# RF_Module.net
KiCad netlist of a schematic drawn in Altium Designer
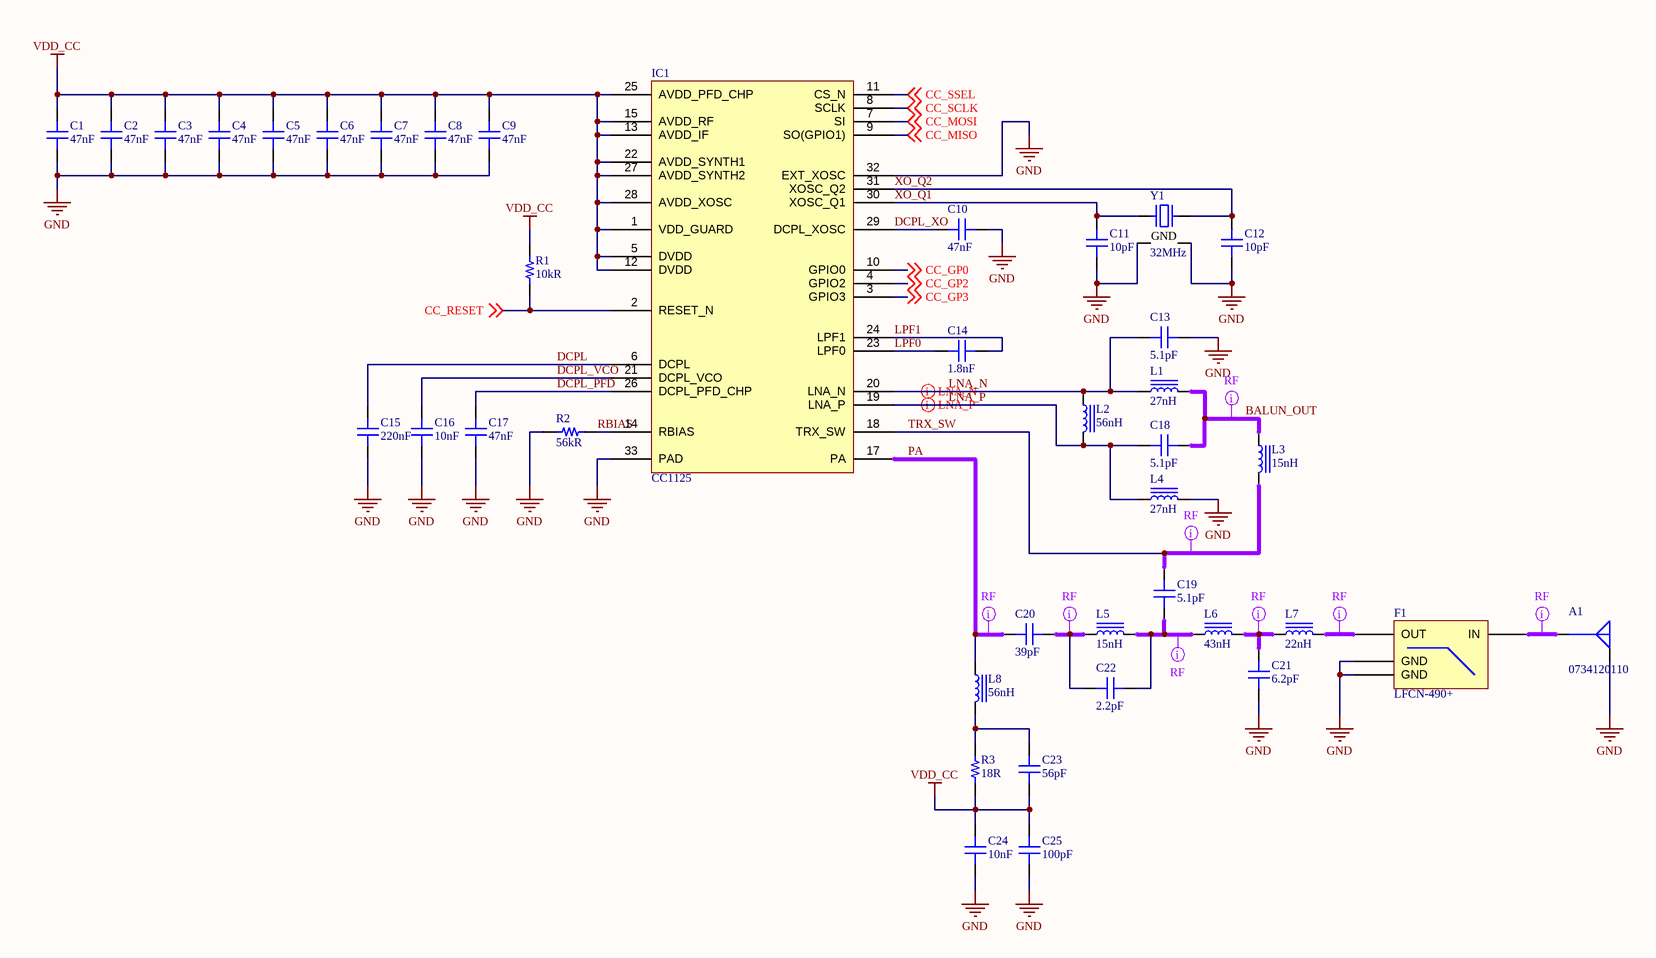
[diagram p0: RF Module.SchDoc]

(export (version "E")
  (design (tool "Eeschema 10.0.6"))
  (components
    (comp (ref "A1")
      (value "0734120110")
      (footprint "MOLEX SD-734120110")
      (description "Conn Micro Coaxial RCP 0Hz to 6GHz 50Ohm Solder ST SMD Gold Embossed T/R")
      (libsource (lib "SCH - RF - ANTENNA - BASIC ANTENNA") (part "Basic Antenna"))
    )
    (comp (ref "C1")
      (value "47nF")
      (footprint "CAP 0402/1005")
      (description "CAP CER 0.047UF 10V X7R 0402")
      (fields (field (name "TOLERANCE") "10%") (field (name "VOLTAGE") "16V"))
      (libsource (lib "SCH - PASSIVES - CAPACITOR") (part "Capacitor"))
    )
    (comp (ref "C2")
      (value "47nF")
      (footprint "CAP 0402/1005")
      (description "CAP CER 0.047UF 10V X7R 0402")
      (fields (field (name "TOLERANCE") "10%") (field (name "VOLTAGE") "16V"))
      (libsource (lib "SCH - PASSIVES - CAPACITOR") (part "Capacitor"))
    )
    (comp (ref "C3")
      (value "47nF")
      (footprint "CAP 0402/1005")
      (description "CAP CER 0.047UF 10V X7R 0402")
      (fields (field (name "TOLERANCE") "10%") (field (name "VOLTAGE") "16V"))
      (libsource (lib "SCH - PASSIVES - CAPACITOR") (part "Capacitor"))
    )
    (comp (ref "C4")
      (value "47nF")
      (footprint "CAP 0402/1005")
      (description "CAP CER 0.047UF 10V X7R 0402")
      (fields (field (name "TOLERANCE") "10%") (field (name "VOLTAGE") "16V"))
      (libsource (lib "SCH - PASSIVES - CAPACITOR") (part "Capacitor"))
    )
    (comp (ref "C5")
      (value "47nF")
      (footprint "CAP 0402/1005")
      (description "CAP CER 0.047UF 10V X7R 0402")
      (fields (field (name "TOLERANCE") "10%") (field (name "VOLTAGE") "16V"))
      (libsource (lib "SCH - PASSIVES - CAPACITOR") (part "Capacitor"))
    )
    (comp (ref "C6")
      (value "47nF")
      (footprint "CAP 0402/1005")
      (description "CAP CER 0.047UF 10V X7R 0402")
      (fields (field (name "TOLERANCE") "10%") (field (name "VOLTAGE") "16V"))
      (libsource (lib "SCH - PASSIVES - CAPACITOR") (part "Capacitor"))
    )
    (comp (ref "C7")
      (value "47nF")
      (footprint "CAP 0402/1005")
      (description "CAP CER 0.047UF 10V X7R 0402")
      (fields (field (name "TOLERANCE") "10%") (field (name "VOLTAGE") "16V"))
      (libsource (lib "SCH - PASSIVES - CAPACITOR") (part "Capacitor"))
    )
    (comp (ref "C8")
      (value "47nF")
      (footprint "CAP 0402/1005")
      (description "CAP CER 0.047UF 10V X7R 0402")
      (fields (field (name "TOLERANCE") "10%") (field (name "VOLTAGE") "16V"))
      (libsource (lib "SCH - PASSIVES - CAPACITOR") (part "Capacitor"))
    )
    (comp (ref "C9")
      (value "47nF")
      (footprint "CAP 0402/1005")
      (description "CAP CER 0.047UF 10V X7R 0402")
      (fields (field (name "TOLERANCE") "10%") (field (name "VOLTAGE") "16V"))
      (libsource (lib "SCH - PASSIVES - CAPACITOR") (part "Capacitor"))
    )
    (comp (ref "C10")
      (value "47nF")
      (footprint "CAP 0402/1005")
      (description "CAP CER 0.047UF 10V X7R 0402")
      (fields (field (name "TOLERANCE") "10%") (field (name "VOLTAGE") "16V"))
      (libsource (lib "SCH - PASSIVES - CAPACITOR") (part "Capacitor"))
    )
    (comp (ref "C11")
      (value "10pF")
      (footprint "CAP 0402/1005")
      (description "CAP CER 10PF 50V C0G/NPO 0402")
      (fields (field (name "TOLERANCE") "5%") (field (name "VOLTAGE") "50V"))
      (libsource (lib "SCH - PASSIVES - CAPACITOR") (part "Capacitor"))
    )
    (comp (ref "C12")
      (value "10pF")
      (footprint "CAP 0402/1005")
      (description "CAP CER 10PF 50V C0G/NPO 0402")
      (fields (field (name "TOLERANCE") "5%") (field (name "VOLTAGE") "50V"))
      (libsource (lib "SCH - PASSIVES - CAPACITOR") (part "Capacitor"))
    )
    (comp (ref "C13")
      (value "5.1pF")
      (footprint "CAP 0402/1005 RF")
      (description "CAP CER 5.1PF 50V C0G/NP0 0402")
      (fields (field (name "VOLTAGE") "50V"))
      (libsource (lib "SCH - PASSIVES - CAPACITOR") (part "Capacitor"))
    )
    (comp (ref "C14")
      (value "1.8nF")
      (footprint "CAP 0402/1005")
      (description "CAP CER 1800PF 50V X7R 0402")
      (fields (field (name "TOLERANCE") "10%"))
      (libsource (lib "SCH - PASSIVES - CAPACITOR") (part "Capacitor"))
    )
    (comp (ref "C15")
      (value "220nF")
      (footprint "CAP 0402/1005")
      (description "Cap Ceramic 0.22uF 10V X7R 10% SMD 0402 125C Paper T/R")
      (fields (field (name "TOLERANCE") "10%"))
      (libsource (lib "SCH - PASSIVES - CAPACITOR") (part "Capacitor"))
    )
    (comp (ref "C16")
      (value "10nF")
      (footprint "CAP 0402/1005")
      (description "TAIYO YUDEN - TMK105B7103KV-F - CERAMIC CAPACITOR 0.01UF, 25V, X7R, 10%, 0402, FULL REEL")
      (fields (field (name "TOLERANCE") "10%") (field (name "VOLTAGE") "25V"))
      (libsource (lib "SCH - PASSIVES - CAPACITOR") (part "Capacitor"))
    )
    (comp (ref "C17")
      (value "47nF")
      (footprint "CAP 0402/1005")
      (description "CAP CER 0.047UF 10V X7R 0402")
      (fields (field (name "TOLERANCE") "10%") (field (name "VOLTAGE") "16V"))
      (libsource (lib "SCH - PASSIVES - CAPACITOR") (part "Capacitor"))
    )
    (comp (ref "C18")
      (value "5.1pF")
      (footprint "CAP 0402/1005 RF")
      (description "CAP CER 5.1PF 50V C0G/NP0 0402")
      (fields (field (name "VOLTAGE") "50V"))
      (libsource (lib "SCH - PASSIVES - CAPACITOR") (part "Capacitor"))
    )
    (comp (ref "C19")
      (value "5.1pF")
      (footprint "CAP 0402/1005 RF")
      (description "CAP CER 5.1PF 50V C0G/NP0 0402")
      (fields (field (name "VOLTAGE") "50V"))
      (libsource (lib "SCH - PASSIVES - CAPACITOR") (part "Capacitor"))
    )
    (comp (ref "C20")
      (value "39pF")
      (footprint "CAP 0402/1005 RF")
      (fields (field (name "TOLERANCE") "5%"))
      (libsource (lib "SCH - PASSIVES - CAPACITOR") (part "Capacitor"))
    )
    (comp (ref "C21")
      (value "6.2pF")
      (footprint "CAP 0402/1005 RF")
      (libsource (lib "SCH - PASSIVES - CAPACITOR") (part "Capacitor"))
    )
    (comp (ref "C22")
      (value "2.2pF")
      (footprint "CAP 0402/1005 RF")
      (fields (field (name "VOLTAGE") "50V"))
      (libsource (lib "SCH - PASSIVES - CAPACITOR") (part "Capacitor"))
    )
    (comp (ref "C23")
      (value "56pF")
      (footprint "CAP 0402/1005 RF")
      (description "Cap Ceramic 56pF 50V C0G 1% SMD 0402 125°C Paper T/R")
      (fields (field (name "TOLERANCE") "1%"))
      (libsource (lib "SCH - PASSIVES - CAPACITOR") (part "Capacitor"))
    )
    (comp (ref "C24")
      (value "10nF")
      (footprint "CAP 0402/1005 RF")
      (description "Cap Ceramic 0.01uF 16V X7R 5% SMD 0402 125C Paper T/R")
      (fields (field (name "TOLERANCE") "5%"))
      (libsource (lib "SCH - PASSIVES - CAPACITOR") (part "Capacitor"))
    )
    (comp (ref "C25")
      (value "100pF")
      (footprint "CAP 0402/1005 RF")
      (description "CAP CER SMD CBR 0402 100PF 5% 25")
      (fields (field (name "TOLERANCE") "5%"))
      (libsource (lib "SCH - PASSIVES - CAPACITOR") (part "Capacitor"))
    )
    (comp (ref "F1")
      (value "LFCN-490+")
      (footprint "PCB - RF FILTER - MINICIRCUITS FV1206")
      (description "490MHz Low Pass Filter")
      (libsource (lib "SCH - RF - FILTER - MINICIRCUITS LFCN-490") (part "SCH - RF - FILTER - MINICIRCUITS LFCN-490"))
    )
    (comp (ref "IC1")
      (value "CC1125")
      (footprint "PCB - LEADLESS - QFN - TI PVQFN-32 5X5MM RHB")
      (description "RF Transceiver Ultra-Hi Perf RF Narrowbd Transceiver")
      (libsource (lib "SCH - RF - IC - TI CC1120") (part "SCH - RF - IC - TI CC1120"))
    )
    (comp (ref "L1")
      (value "27nH")
      (footprint "IND 0402/1005 RF WW")
      (fields (field (name "TOLERANCE") "2%"))
      (libsource (lib "SCH - PASSIVES - INDUCTOR") (part "Inductor"))
    )
    (comp (ref "L2")
      (value "56nH")
      (footprint "IND 0402/1005 RF WW")
      (description "Fixed Inductors 56nH 2%")
      (fields (field (name "TOLERANCE") "2%"))
      (libsource (lib "SCH - PASSIVES - INDUCTOR") (part "Inductor"))
    )
    (comp (ref "L3")
      (value "15nH")
      (footprint "IND 0402/1005 RF WW")
      (description "FIXED IND 15NH 1.15A 114 MOHM")
      (fields (field (name "TOLERANCE") "2%"))
      (libsource (lib "SCH - PASSIVES - INDUCTOR") (part "Inductor"))
    )
    (comp (ref "L4")
      (value "27nH")
      (footprint "IND 0402/1005 RF WW")
      (fields (field (name "TOLERANCE") "2%"))
      (libsource (lib "SCH - PASSIVES - INDUCTOR") (part "Inductor"))
    )
    (comp (ref "L5")
      (value "15nH")
      (footprint "IND 0402/1005 RF WW")
      (description "FIXED IND 15NH 1.15A 114 MOHM")
      (fields (field (name "TOLERANCE") "2%"))
      (libsource (lib "SCH - PASSIVES - INDUCTOR") (part "Inductor"))
    )
    (comp (ref "L6")
      (value "43nH")
      (footprint "IND 0402/1005 RF WW")
      (description "Fixed Inductors 43nH 2% 100MHz")
      (fields (field (name "TOLERANCE") "2%"))
      (libsource (lib "SCH - PASSIVES - INDUCTOR") (part "Inductor"))
    )
    (comp (ref "L7")
      (value "22nH")
      (footprint "IND 0402/1005 RF WW")
      (description "FIXED IND 22NH 780MA 202 MOHM")
      (fields (field (name "TOLERANCE") "2%"))
      (libsource (lib "SCH - PASSIVES - INDUCTOR") (part "Inductor"))
    )
    (comp (ref "L8")
      (value "56nH")
      (footprint "IND 0402/1005 RF WW")
      (description "Fixed Inductors 56nH 2%")
      (fields (field (name "TOLERANCE") "2%"))
      (libsource (lib "SCH - PASSIVES - INDUCTOR") (part "Inductor"))
    )
    (comp (ref "R1")
      (value "10kR")
      (footprint "RES 0402/1005")
      (description "RES SMD 10K OHM 5% 1/16W 0402")
      (fields (field (name "TOLERANCE") "5%"))
      (libsource (lib "SCH - PASSIVES - RESISTOR") (part "Resistor"))
    )
    (comp (ref "R2")
      (value "56kR")
      (footprint "RES 0402/1005")
      (description "RES SMD 56K OHM 5% 1/16W 0402")
      (fields (field (name "TOLERANCE") "5%"))
      (libsource (lib "SCH - PASSIVES - RESISTOR") (part "Resistor"))
    )
    (comp (ref "R3")
      (value "18R")
      (footprint "RES 0402/1005")
      (fields (field (name "TOLERANCE") "1%"))
      (libsource (lib "SCH - PASSIVES - RESISTOR") (part "Resistor"))
    )
    (comp (ref "Y1")
      (value "32MHz")
      (footprint "ABRACON ABM8G")
      (description "CRYSTAL 32.0000MHZ 10PF SMD")
      (fields (field (name "TOLERANCE") "30ppm"))
      (libsource (lib "SCH - CRYSTALS - ABRACON CRYSTAL ABM8G") (part "Abracon Crystal ABM8G"))
    )
  )
  (nets
    (net (code "1") (name "/BALUN_OUT") (class "Default")
      (node (ref "C18") (pin "2") (pinfunction "2_2") (pintype "passive"))
      (node (ref "L1") (pin "2") (pinfunction "2_2") (pintype "passive"))
      (node (ref "L3") (pin "1") (pinfunction "1_1") (pintype "passive"))
    )
    (net (code "2") (name "/DCPL") (class "Default")
      (node (ref "C15") (pin "2") (pinfunction "2_2") (pintype "passive"))
      (node (ref "IC1") (pin "6") (pinfunction "DCPL_6") (pintype "passive"))
    )
    (net (code "3") (name "/DCPL_PFD") (class "Default")
      (node (ref "C17") (pin "2") (pinfunction "2_2") (pintype "passive"))
      (node (ref "IC1") (pin "26") (pinfunction "DCPL_PFD_CHP_26") (pintype "passive"))
    )
    (net (code "4") (name "/DCPL_VCO") (class "Default")
      (node (ref "C16") (pin "2") (pinfunction "2_2") (pintype "passive"))
      (node (ref "IC1") (pin "21") (pinfunction "DCPL_VCO_21") (pintype "passive"))
    )
    (net (code "5") (name "/DCPL_XO") (class "Default")
      (node (ref "C10") (pin "2") (pinfunction "2_2") (pintype "passive"))
      (node (ref "IC1") (pin "29") (pinfunction "DCPL_XOSC_29") (pintype "passive"))
    )
    (net (code "6") (name "/LNA_N") (class "Default")
      (node (ref "C13") (pin "1") (pinfunction "1_1") (pintype "passive"))
      (node (ref "IC1") (pin "20") (pinfunction "LNA_N_20") (pintype "passive"))
      (node (ref "L1") (pin "1") (pinfunction "1_1") (pintype "passive"))
      (node (ref "L2") (pin "1") (pinfunction "1_1") (pintype "passive"))
    )
    (net (code "7") (name "/LNA_P") (class "Default")
      (node (ref "C18") (pin "1") (pinfunction "1_1") (pintype "passive"))
      (node (ref "IC1") (pin "19") (pinfunction "LNA_P_19") (pintype "passive"))
      (node (ref "L2") (pin "2") (pinfunction "2_2") (pintype "passive"))
      (node (ref "L4") (pin "1") (pinfunction "1_1") (pintype "passive"))
    )
    (net (code "8") (name "/LPF0") (class "Default")
      (node (ref "C14") (pin "2") (pinfunction "2_2") (pintype "passive"))
      (node (ref "IC1") (pin "23") (pinfunction "LPF0_23") (pintype "passive"))
    )
    (net (code "9") (name "/LPF1") (class "Default")
      (node (ref "C14") (pin "1") (pinfunction "1_1") (pintype "passive"))
      (node (ref "IC1") (pin "24") (pinfunction "LPF1_24") (pintype "passive"))
    )
    (net (code "10") (name "/PA") (class "Default")
      (node (ref "C20") (pin "1") (pinfunction "1_1") (pintype "passive"))
      (node (ref "IC1") (pin "17") (pinfunction "PA_17") (pintype "passive"))
      (node (ref "L8") (pin "1") (pinfunction "1_1") (pintype "passive"))
    )
    (net (code "11") (name "/RBIAS") (class "Default")
      (node (ref "IC1") (pin "14") (pinfunction "RBIAS_14") (pintype "passive"))
      (node (ref "R2") (pin "1") (pinfunction "1_1") (pintype "passive"))
    )
    (net (code "12") (name "/TRX_SW") (class "Default")
      (node (ref "C19") (pin "2") (pinfunction "2_2") (pintype "passive"))
      (node (ref "IC1") (pin "18") (pinfunction "TRX_SW_18") (pintype "passive"))
      (node (ref "L3") (pin "2") (pinfunction "2_2") (pintype "passive"))
    )
    (net (code "13") (name "/XO_Q1") (class "Default")
      (node (ref "C11") (pin "2") (pinfunction "2_2") (pintype "passive"))
      (node (ref "IC1") (pin "30") (pinfunction "XOSC_Q1_30") (pintype "passive"))
      (node (ref "Y1") (pin "1") (pinfunction "1_1") (pintype "passive"))
    )
    (net (code "14") (name "/XO_Q2") (class "Default")
      (node (ref "C12") (pin "2") (pinfunction "2_2") (pintype "passive"))
      (node (ref "IC1") (pin "31") (pinfunction "XOSC_Q2_31") (pintype "passive"))
      (node (ref "Y1") (pin "3") (pinfunction "3_3") (pintype "passive"))
    )
    (net (code "15") (name "CC_GP0") (class "Default")
      (node (ref "IC1") (pin "10") (pinfunction "GPIO0_10") (pintype "passive"))
    )
    (net (code "16") (name "CC_GP2") (class "Default")
      (node (ref "IC1") (pin "4") (pinfunction "GPIO2_4") (pintype "passive"))
    )
    (net (code "17") (name "CC_GP3") (class "Default")
      (node (ref "IC1") (pin "3") (pinfunction "GPIO3_3") (pintype "passive"))
    )
    (net (code "18") (name "CC_MISO") (class "Default")
      (node (ref "IC1") (pin "9") (pinfunction "SO(GPIO1)_9") (pintype "passive"))
    )
    (net (code "19") (name "CC_MOSI") (class "Default")
      (node (ref "IC1") (pin "7") (pinfunction "SI_7") (pintype "passive"))
    )
    (net (code "20") (name "CC_RESET") (class "Default")
      (node (ref "IC1") (pin "2") (pinfunction "RESET_N_2") (pintype "passive"))
      (node (ref "R1") (pin "1") (pinfunction "1_1") (pintype "passive"))
    )
    (net (code "21") (name "CC_SCLK") (class "Default")
      (node (ref "IC1") (pin "8") (pinfunction "SCLK_8") (pintype "passive"))
    )
    (net (code "22") (name "CC_SSEL") (class "Default")
      (node (ref "IC1") (pin "11") (pinfunction "CS_N_11") (pintype "passive"))
    )
    (net (code "23") (name "GND") (class "Default")
      (node (ref "A1") (pin "G") (pinfunction "G_G") (pintype "passive"))
      (node (ref "C1") (pin "1") (pinfunction "1_1") (pintype "passive"))
      (node (ref "C10") (pin "1") (pinfunction "1_1") (pintype "passive"))
      (node (ref "C11") (pin "1") (pinfunction "1_1") (pintype "passive"))
      (node (ref "C12") (pin "1") (pinfunction "1_1") (pintype "passive"))
      (node (ref "C13") (pin "2") (pinfunction "2_2") (pintype "passive"))
      (node (ref "C15") (pin "1") (pinfunction "1_1") (pintype "passive"))
      (node (ref "C16") (pin "1") (pinfunction "1_1") (pintype "passive"))
      (node (ref "C17") (pin "1") (pinfunction "1_1") (pintype "passive"))
      (node (ref "C2") (pin "1") (pinfunction "1_1") (pintype "passive"))
      (node (ref "C21") (pin "1") (pinfunction "1_1") (pintype "passive"))
      (node (ref "C24") (pin "1") (pinfunction "1_1") (pintype "passive"))
      (node (ref "C25") (pin "1") (pinfunction "1_1") (pintype "passive"))
      (node (ref "C3") (pin "1") (pinfunction "1_1") (pintype "passive"))
      (node (ref "C4") (pin "1") (pinfunction "1_1") (pintype "passive"))
      (node (ref "C5") (pin "1") (pinfunction "1_1") (pintype "passive"))
      (node (ref "C6") (pin "1") (pinfunction "1_1") (pintype "passive"))
      (node (ref "C7") (pin "1") (pinfunction "1_1") (pintype "passive"))
      (node (ref "C8") (pin "1") (pinfunction "1_1") (pintype "passive"))
      (node (ref "C9") (pin "1") (pinfunction "1_1") (pintype "passive"))
      (node (ref "F1") (pin "2") (pinfunction "GND_2") (pintype "passive"))
      (node (ref "F1") (pin "4") (pinfunction "GND_4") (pintype "passive"))
      (node (ref "IC1") (pin "32") (pinfunction "EXT_XOSC_32") (pintype "passive"))
      (node (ref "IC1") (pin "33") (pinfunction "PAD_33") (pintype "passive"))
      (node (ref "L4") (pin "2") (pinfunction "2_2") (pintype "passive"))
      (node (ref "R2") (pin "2") (pinfunction "2_2") (pintype "passive"))
      (node (ref "Y1") (pin "2") (pinfunction "GND_2") (pintype "passive"))
      (node (ref "Y1") (pin "4") (pinfunction "GND_4") (pintype "passive"))
    )
    (net (code "24") (name "Net-(C19-Pad1)") (class "Default")
      (node (ref "C19") (pin "1") (pinfunction "1_1") (pintype "passive"))
      (node (ref "C22") (pin "1") (pinfunction "1_1") (pintype "passive"))
      (node (ref "L5") (pin "2") (pinfunction "2_2") (pintype "passive"))
      (node (ref "L6") (pin "1") (pinfunction "1_1") (pintype "passive"))
    )
    (net (code "25") (name "Net-(C20-Pad2)") (class "Default")
      (node (ref "C20") (pin "2") (pinfunction "2_2") (pintype "passive"))
      (node (ref "C22") (pin "2") (pinfunction "2_2") (pintype "passive"))
      (node (ref "L5") (pin "1") (pinfunction "1_1") (pintype "passive"))
    )
    (net (code "26") (name "Net-(C21-Pad2)") (class "Default")
      (node (ref "C21") (pin "2") (pinfunction "2_2") (pintype "passive"))
      (node (ref "L6") (pin "2") (pinfunction "2_2") (pintype "passive"))
      (node (ref "L7") (pin "1") (pinfunction "1_1") (pintype "passive"))
    )
    (net (code "27") (name "Net-(C23-Pad2)") (class "Default")
      (node (ref "C23") (pin "2") (pinfunction "2_2") (pintype "passive"))
      (node (ref "L8") (pin "2") (pinfunction "2_2") (pintype "passive"))
      (node (ref "R3") (pin "2") (pinfunction "2_2") (pintype "passive"))
    )
    (net (code "28") (name "Net-(F1-IN)") (class "Default")
      (node (ref "A1") (pin "S") (pinfunction "S_S") (pintype "passive"))
      (node (ref "F1") (pin "1") (pinfunction "IN_1") (pintype "passive"))
    )
    (net (code "29") (name "Net-(F1-OUT)") (class "Default")
      (node (ref "F1") (pin "3") (pinfunction "OUT_3") (pintype "passive"))
      (node (ref "L7") (pin "2") (pinfunction "2_2") (pintype "passive"))
    )
    (net (code "30") (name "VDD_CC") (class "Default")
      (node (ref "C1") (pin "2") (pinfunction "2_2") (pintype "passive"))
      (node (ref "C2") (pin "2") (pinfunction "2_2") (pintype "passive"))
      (node (ref "C23") (pin "1") (pinfunction "1_1") (pintype "passive"))
      (node (ref "C24") (pin "2") (pinfunction "2_2") (pintype "passive"))
      (node (ref "C25") (pin "2") (pinfunction "2_2") (pintype "passive"))
      (node (ref "C3") (pin "2") (pinfunction "2_2") (pintype "passive"))
      (node (ref "C4") (pin "2") (pinfunction "2_2") (pintype "passive"))
      (node (ref "C5") (pin "2") (pinfunction "2_2") (pintype "passive"))
      (node (ref "C6") (pin "2") (pinfunction "2_2") (pintype "passive"))
      (node (ref "C7") (pin "2") (pinfunction "2_2") (pintype "passive"))
      (node (ref "C8") (pin "2") (pinfunction "2_2") (pintype "passive"))
      (node (ref "C9") (pin "2") (pinfunction "2_2") (pintype "passive"))
      (node (ref "IC1") (pin "1") (pinfunction "VDD_GUARD_1") (pintype "passive"))
      (node (ref "IC1") (pin "12") (pinfunction "DVDD_12") (pintype "passive"))
      (node (ref "IC1") (pin "13") (pinfunction "AVDD_IF_13") (pintype "passive"))
      (node (ref "IC1") (pin "15") (pinfunction "AVDD_RF_15") (pintype "passive"))
      (node (ref "IC1") (pin "22") (pinfunction "AVDD_SYNTH1_22") (pintype "passive"))
      (node (ref "IC1") (pin "25") (pinfunction "AVDD_PFD_CHP_25") (pintype "passive"))
      (node (ref "IC1") (pin "27") (pinfunction "AVDD_SYNTH2_27") (pintype "passive"))
      (node (ref "IC1") (pin "28") (pinfunction "AVDD_XOSC_28") (pintype "passive"))
      (node (ref "IC1") (pin "5") (pinfunction "DVDD_5") (pintype "passive"))
      (node (ref "R1") (pin "2") (pinfunction "2_2") (pintype "passive"))
      (node (ref "R3") (pin "1") (pinfunction "1_1") (pintype "passive"))
    )
  )
)
